# ASBB_SPICrossbar.net
KiCad netlist of a schematic drawn in Altium Designer
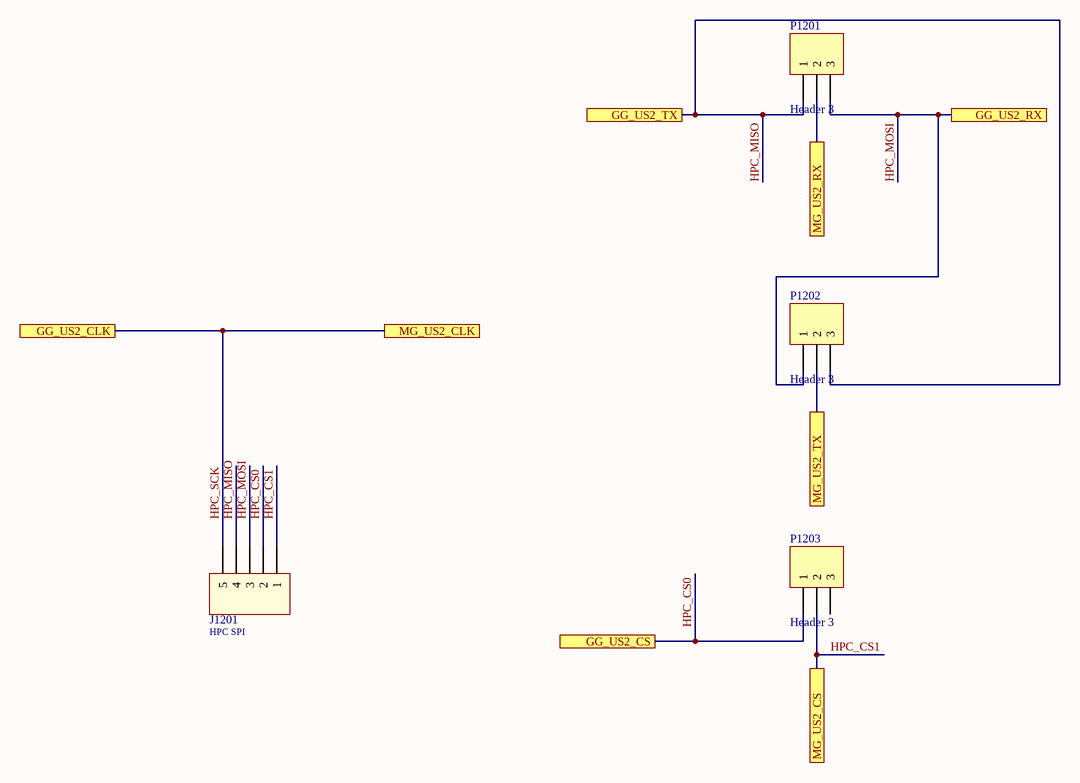
[diagram p0: ASBB_SPICrossbar.SchDoc]

(export (version "E")
  (design (tool "Eeschema 10.0.6"))
  (components
    (comp (ref "J1201")
      (value "HPC SPI")
      (footprint "61000511921")
      (description "Socket Header WR-PHD, Pitch 2.54 mm, SMT, Vertical, single row, 5 pin")
      (fields (field (name "PART NUMBER") "61000511921") (field (name "PUBLISHER") "Wurth Elektronik"))
      (libsource (lib "6220xx21821 (rev18a)") (part "61000511921"))
    )
    (comp (ref "P1201")
      (value "Header 3")
      (footprint "HDR1X3")
      (description "Header, 3-Pin")
      (fields (field (name "PUBLISHER") "Altium Limited"))
      (libsource (lib "Miscellaneous Connectors") (part "Header 3"))
    )
    (comp (ref "P1202")
      (value "Header 3")
      (footprint "HDR1X3")
      (description "Header, 3-Pin")
      (fields (field (name "PUBLISHER") "Altium Limited"))
      (libsource (lib "Miscellaneous Connectors") (part "Header 3"))
    )
    (comp (ref "P1203")
      (value "Header 3")
      (footprint "HDR1X3")
      (description "Header, 3-Pin")
      (fields (field (name "PUBLISHER") "Altium Limited"))
      (libsource (lib "Miscellaneous Connectors") (part "Header 3"))
    )
  )
  (nets
    (net (code "1") (name "/HPC_CS0") (class "Default")
      (node (ref "J1201") (pin "2") (pinfunction "2_2") (pintype "passive"))
      (node (ref "P1203") (pin "1") (pinfunction "1_1") (pintype "passive"))
    )
    (net (code "2") (name "/HPC_CS1") (class "Default")
      (node (ref "J1201") (pin "1") (pinfunction "1_1") (pintype "passive"))
      (node (ref "P1203") (pin "2") (pinfunction "2_2") (pintype "passive"))
    )
    (net (code "3") (name "/HPC_MISO") (class "Default")
      (node (ref "J1201") (pin "4") (pinfunction "4_4") (pintype "passive"))
      (node (ref "P1201") (pin "1") (pinfunction "1_1") (pintype "passive"))
      (node (ref "P1202") (pin "3") (pinfunction "3_3") (pintype "passive"))
    )
    (net (code "4") (name "/HPC_MOSI") (class "Default")
      (node (ref "J1201") (pin "3") (pinfunction "3_3") (pintype "passive"))
      (node (ref "P1201") (pin "3") (pinfunction "3_3") (pintype "passive"))
      (node (ref "P1202") (pin "1") (pinfunction "1_1") (pintype "passive"))
    )
    (net (code "5") (name "/HPC_SCK") (class "Default")
      (node (ref "J1201") (pin "5") (pinfunction "5_5") (pintype "passive"))
    )
    (net (code "6") (name "/MG_US2_RX") (class "Default")
      (node (ref "P1201") (pin "2") (pinfunction "2_2") (pintype "passive"))
    )
    (net (code "7") (name "/MG_US2_TX") (class "Default")
      (node (ref "P1202") (pin "2") (pinfunction "2_2") (pintype "passive"))
    )
    (net (code "8") (name "unconnected-(P1203-Pad3)") (class "Default")
      (node (ref "P1203") (pin "3") (pinfunction "3_3") (pintype "passive"))
    )
  )
)
